# 555_Timer.net
KiCad netlist of a schematic drawn in Altium Designer
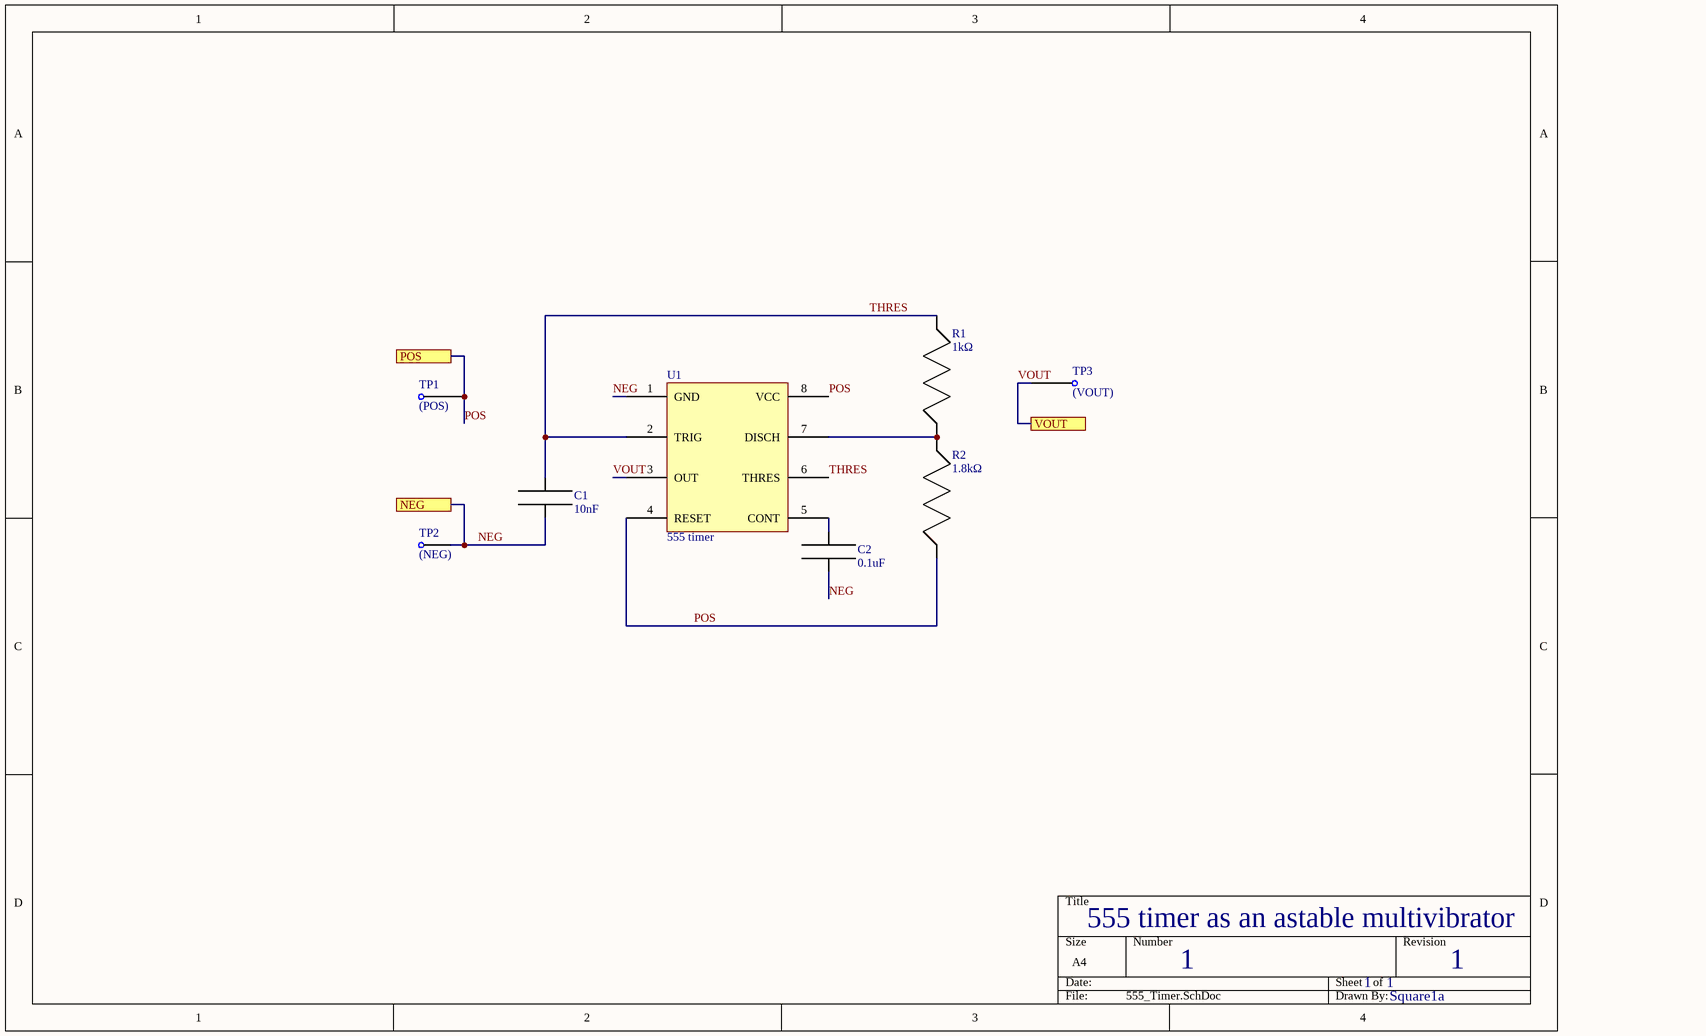
[diagram p0: 555_Timer.SchDoc]

(export (version "E")
  (design (tool "Eeschema 10.0.6"))
  (components
    (comp (ref "C1")
      (value "10nF")
      (footprint "Capacitor")
      (description "Cap Ceramic 0.01uF 100V X7R 10% SMD 0603 125°C Paper T/R")
      (fields
        (field (name "MANUFACTURER") "KEMET")
        (field (name "MANUFACTURER PART NUMBER") "C0603X103K1RAC3316")
      )
      (libsource (lib "Schlib1") (part "C0603X103K1RAC3316"))
    )
    (comp (ref "C2")
      (value "0.1uF")
      (footprint "Capacitor")
      (description "Cap, 0.1ΜF, 10V, 10%, X7R, 1206")
      (fields
        (field (name "MANUFACTURER") "Wurth Electronics")
        (field (name "MANUFACTURER PART NUMBER") "885012208009")
      )
      (libsource (lib "Schlib1") (part "885012208009"))
    )
    (comp (ref "R1")
      (value "1kΩ")
      (footprint "Through hole resistor")
      (description "Res Metal Film 1K Ohm 5% 2/5W ±100ppm/°C Conformal AXL Thru-Hole Ammo Pack")
      (fields
        (field (name "MANUFACTURER") "Vishay BCcomponents")
        (field (name "MANUFACTURER PART NUMBER") "SFR2500001001JA500")
      )
      (libsource (lib "Schlib1") (part "SFR2500001001JA500"))
    )
    (comp (ref "R2")
      (value "1.8kΩ")
      (footprint "Through hole resistor")
      (description "General Type Metal Film Resistor 1.8kOhm 1/4W 1% Axial Ammo Pack")
      (fields
        (field (name "MANUFACTURER") "Yageo")
        (field (name "MANUFACTURER PART NUMBER") "MFR-25FTE52-1K8")
      )
      (libsource (lib "Schlib1") (part "MFR-25FTE52-1K8"))
    )
    (comp (ref "TP1")
      (value "(POS)")
      (footprint "TEST_POINT")
      (description "Polyurethane Multi-Purpose Cream Adhesive, 10.3 oz Cartridge")
      (fields
        (field (name "MANUFACTURER") "Keystone Electronics")
        (field (name "MANUFACTURER PART NUMBER") "5010")
      )
      (libsource (lib "Schlib1") (part "5010"))
    )
    (comp (ref "TP2")
      (value "(NEG)")
      (footprint "TEST_POINT")
      (description "Test Point MultiPurpose THM H .445 Nylon 46 Insulated Blk PhosBronze/Silver")
      (fields
        (field (name "MANUFACTURER") "Keystone Electronics")
        (field (name "MANUFACTURER PART NUMBER") "5011")
      )
      (libsource (lib "Schlib1") (part "5011"))
    )
    (comp (ref "TP3")
      (value "(VOUT)")
      (footprint "TEST_POINT")
      (description "Test Point MultiPurpose THM H .445 Nylon 46 Insulated Yel PhosBronze/Silver")
      (fields
        (field (name "MANUFACTURER") "Keystone Electronics")
        (field (name "MANUFACTURER PART NUMBER") "5014")
      )
      (libsource (lib "Schlib1") (part "5014"))
    )
    (comp (ref "U1")
      (value "555 timer")
      (footprint "DIP8")
      (description "IC OSC SINGLE TIMER 100KHZ 8-DIP")
      (fields
        (field (name "MANUFACTURER") "Texas Instruments")
        (field (name "MANUFACTURER PART NUMBER") "NE555P")
      )
      (libsource (lib "Schlib1") (part "NE555P"))
    )
  )
  (nets
    (net (code "1") (name "/NEG") (class "Default")
      (node (ref "C1") (pin "1") (pinfunction "1_1") (pintype "passive"))
      (node (ref "C2") (pin "1") (pinfunction "1_1") (pintype "passive"))
      (node (ref "TP2") (pin "1") (pinfunction "1_1") (pintype "passive"))
      (node (ref "U1") (pin "1") (pinfunction "GND_1") (pintype "passive"))
    )
    (net (code "2") (name "/POS") (class "Default")
      (node (ref "R2") (pin "1") (pinfunction "1_1") (pintype "passive"))
      (node (ref "TP1") (pin "1") (pinfunction "1_1") (pintype "passive"))
      (node (ref "U1") (pin "4") (pinfunction "RESET_4") (pintype "passive"))
      (node (ref "U1") (pin "8") (pinfunction "VCC_8") (pintype "passive"))
    )
    (net (code "3") (name "/THRES") (class "Default")
      (node (ref "C1") (pin "2") (pinfunction "2_2") (pintype "passive"))
      (node (ref "R1") (pin "2") (pinfunction "2_2") (pintype "passive"))
      (node (ref "U1") (pin "2") (pinfunction "TRIG_2") (pintype "passive"))
      (node (ref "U1") (pin "6") (pinfunction "THRES_6") (pintype "passive"))
    )
    (net (code "4") (name "/VOUT") (class "Default")
      (node (ref "TP3") (pin "1") (pinfunction "1_1") (pintype "passive"))
      (node (ref "U1") (pin "3") (pinfunction "OUT_3") (pintype "passive"))
    )
    (net (code "5") (name "Net-(U1-CONT)") (class "Default")
      (node (ref "C2") (pin "2") (pinfunction "2_2") (pintype "passive"))
      (node (ref "U1") (pin "5") (pinfunction "CONT_5") (pintype "passive"))
    )
    (net (code "6") (name "Net-(U1-DISCH)") (class "Default")
      (node (ref "R1") (pin "1") (pinfunction "1_1") (pintype "passive"))
      (node (ref "R2") (pin "2") (pinfunction "2_2") (pintype "passive"))
      (node (ref "U1") (pin "7") (pinfunction "DISCH_7") (pintype "passive"))
    )
  )
)
